# 03-ETHERNET.net
KiCad netlist of a schematic drawn in Altium Designer
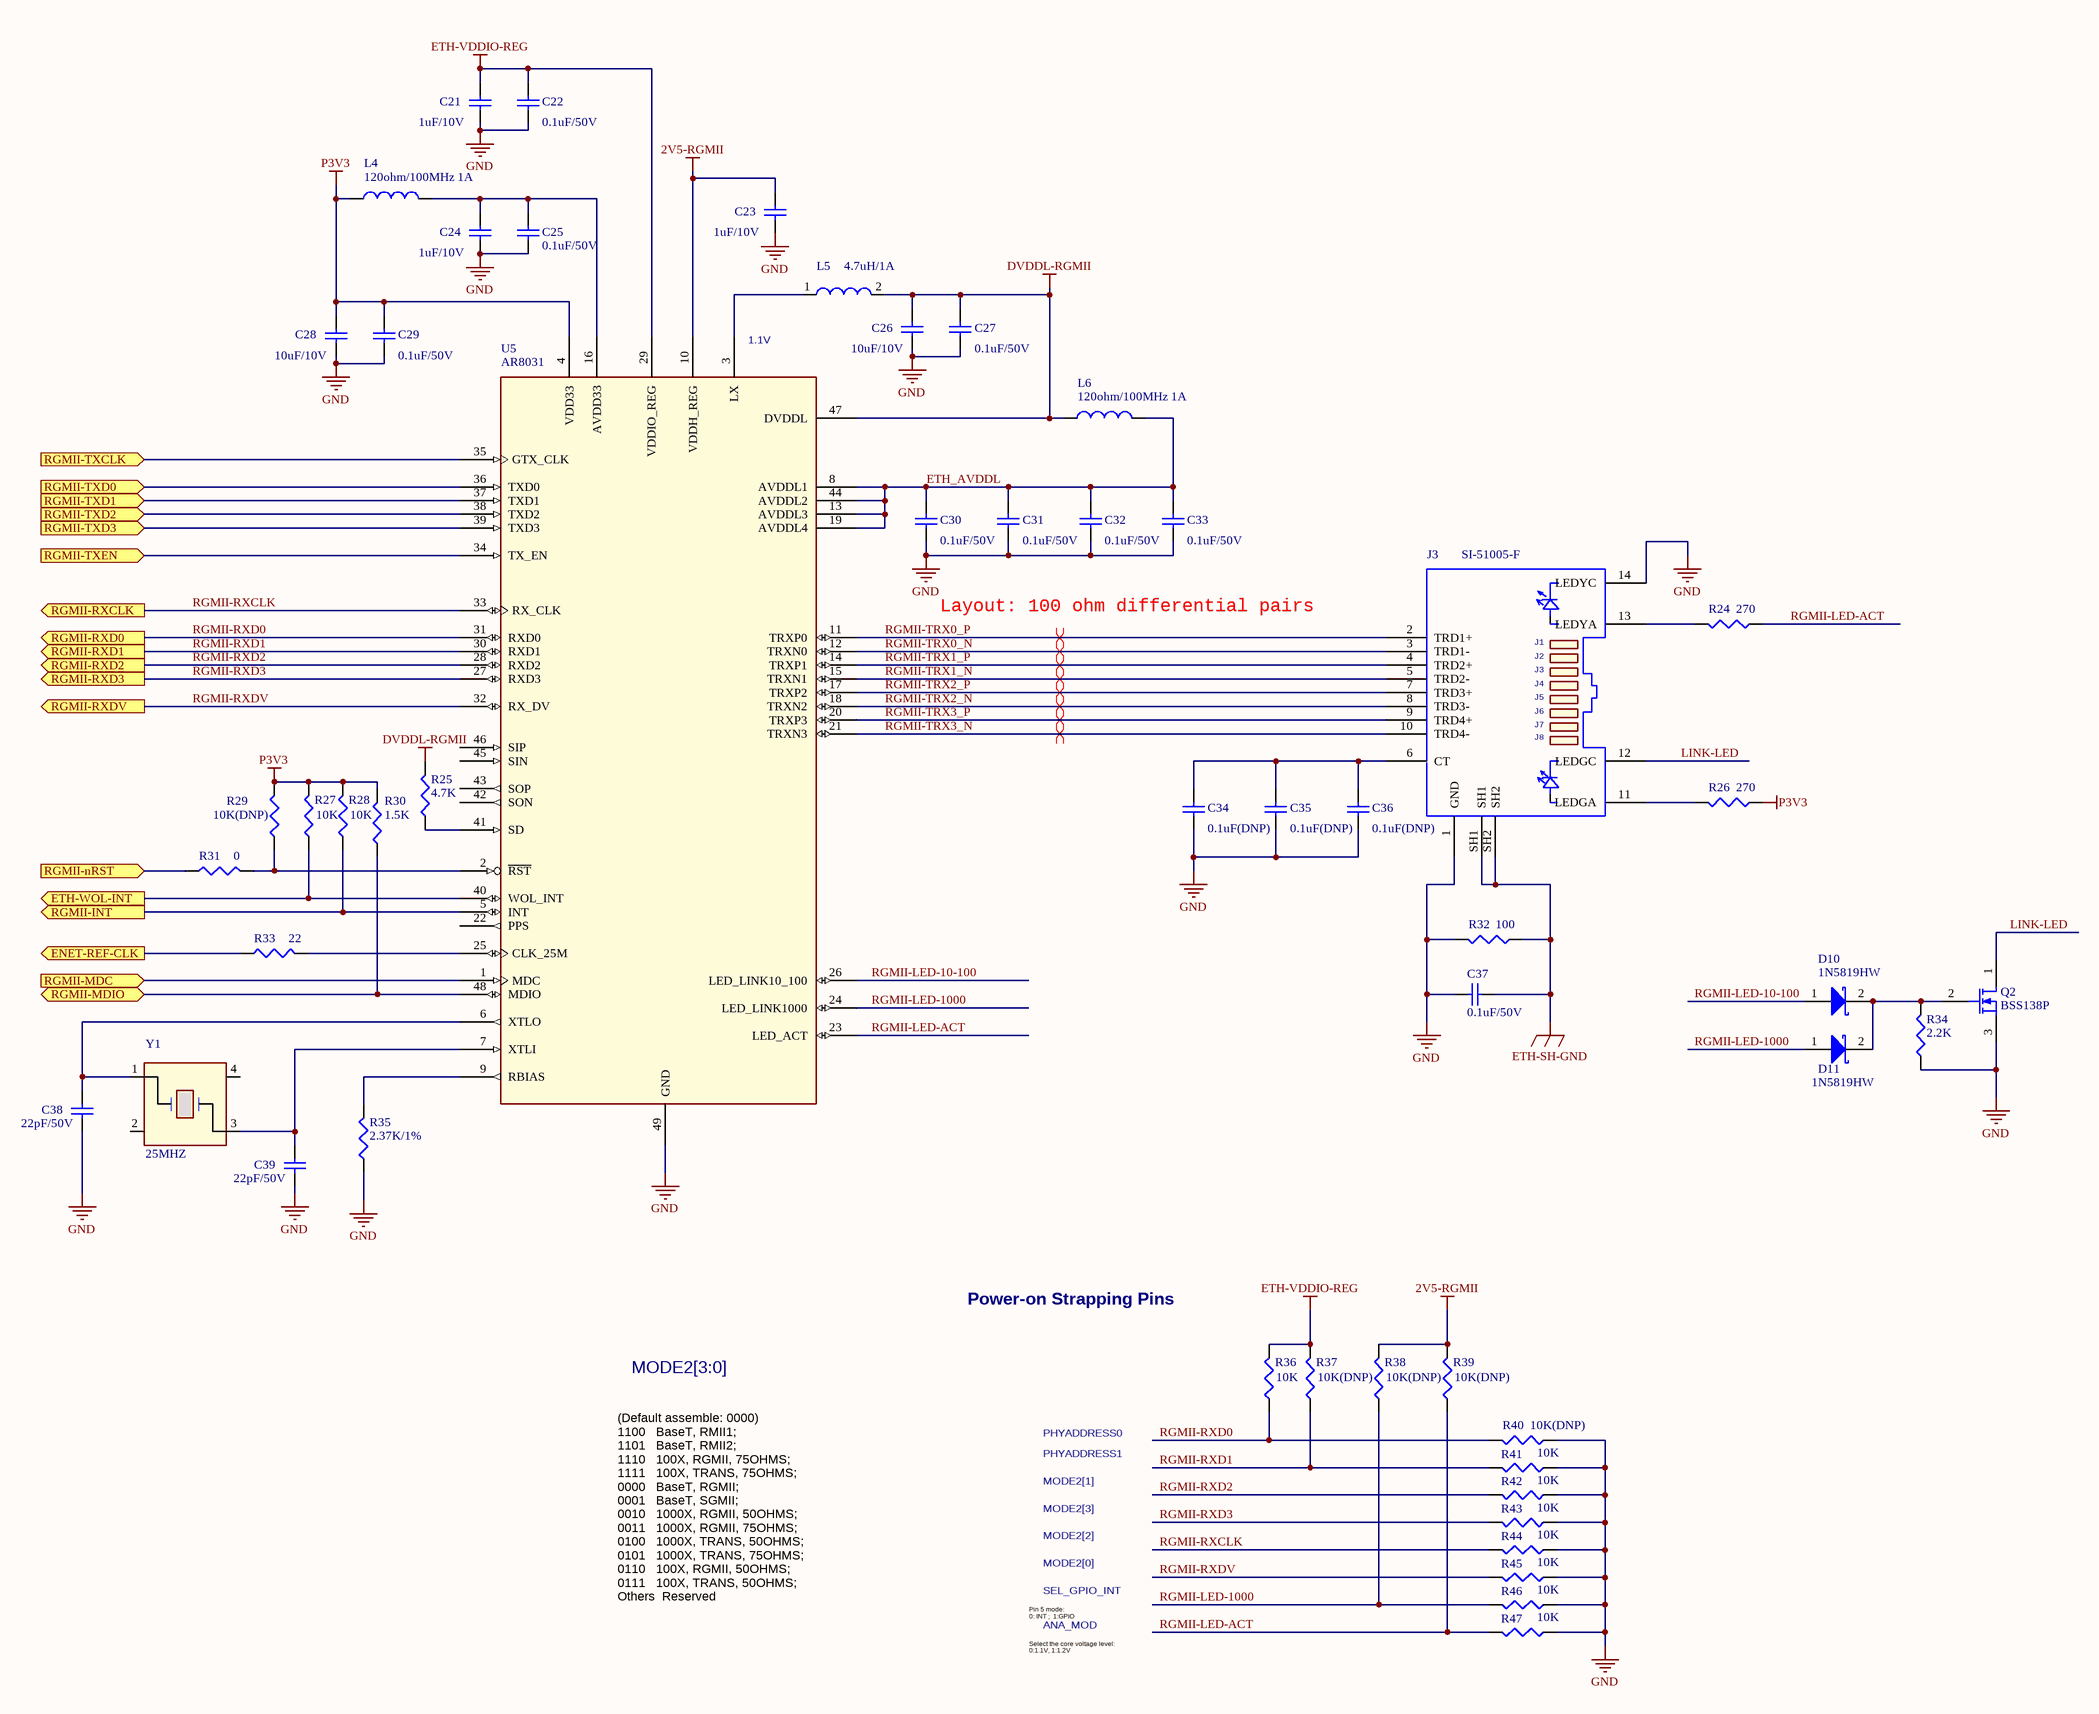
[diagram p0: 03-ETHERNET.SchDoc]

(export (version "E")
  (design (tool "Eeschema 10.0.6"))
  (components
    (comp (ref "C21")
      (value "1uF/10V")
      (footprint "0402")
      (description "Capacitor")
      (fields (field (name "PUBLISHER") "Altium Limited"))
      (libsource (lib "Miscellaneous Devices") (part "Cap"))
    )
    (comp (ref "C22")
      (value "0.1uF/50V")
      (footprint "0402")
      (description "Capacitor")
      (fields (field (name "PUBLISHER") "Altium Limited"))
      (libsource (lib "Miscellaneous Devices") (part "Cap"))
    )
    (comp (ref "C23")
      (value "1uF/10V")
      (footprint "0402")
      (description "Capacitor")
      (fields (field (name "PUBLISHER") "Altium Limited"))
      (libsource (lib "Miscellaneous Devices") (part "Cap"))
    )
    (comp (ref "C24")
      (value "1uF/10V")
      (footprint "0402")
      (description "Capacitor")
      (fields (field (name "PUBLISHER") "Altium Limited"))
      (libsource (lib "Miscellaneous Devices") (part "Cap"))
    )
    (comp (ref "C25")
      (value "0.1uF/50V")
      (footprint "0402")
      (description "Capacitor")
      (fields (field (name "PUBLISHER") "Altium Limited"))
      (libsource (lib "Miscellaneous Devices") (part "Cap"))
    )
    (comp (ref "C26")
      (value "10uF/10V")
      (footprint "0805")
      (description "Capacitor")
      (fields (field (name "PUBLISHER") "Altium Limited"))
      (libsource (lib "Miscellaneous Devices") (part "Cap"))
    )
    (comp (ref "C27")
      (value "0.1uF/50V")
      (footprint "0402")
      (description "Capacitor")
      (fields (field (name "PUBLISHER") "Altium Limited"))
      (libsource (lib "Miscellaneous Devices") (part "Cap"))
    )
    (comp (ref "C28")
      (value "10uF/10V")
      (footprint "0805")
      (description "Capacitor")
      (fields (field (name "PUBLISHER") "Altium Limited"))
      (libsource (lib "Miscellaneous Devices") (part "Cap"))
    )
    (comp (ref "C29")
      (value "0.1uF/50V")
      (footprint "0402")
      (description "Capacitor")
      (fields (field (name "PUBLISHER") "Altium Limited"))
      (libsource (lib "Miscellaneous Devices") (part "Cap"))
    )
    (comp (ref "C30")
      (value "0.1uF/50V")
      (footprint "0402")
      (description "Capacitor")
      (fields (field (name "PUBLISHER") "Altium Limited"))
      (libsource (lib "Miscellaneous Devices") (part "Cap"))
    )
    (comp (ref "C31")
      (value "0.1uF/50V")
      (footprint "0402")
      (description "Capacitor")
      (fields (field (name "PUBLISHER") "Altium Limited"))
      (libsource (lib "Miscellaneous Devices") (part "Cap"))
    )
    (comp (ref "C32")
      (value "0.1uF/50V")
      (footprint "0402")
      (description "Capacitor")
      (fields (field (name "PUBLISHER") "Altium Limited"))
      (libsource (lib "Miscellaneous Devices") (part "Cap"))
    )
    (comp (ref "C33")
      (value "0.1uF/50V")
      (footprint "0402")
      (description "Capacitor")
      (fields (field (name "PUBLISHER") "Altium Limited"))
      (libsource (lib "Miscellaneous Devices") (part "Cap"))
    )
    (comp (ref "C34")
      (value "0.1uF(DNP)")
      (footprint "0603")
      (description "Capacitor")
      (fields (field (name "PUBLISHER") "Altium Limited"))
      (libsource (lib "Miscellaneous Devices") (part "Cap"))
    )
    (comp (ref "C35")
      (value "0.1uF(DNP)")
      (footprint "0603")
      (description "Capacitor")
      (fields (field (name "PUBLISHER") "Altium Limited"))
      (libsource (lib "Miscellaneous Devices") (part "Cap"))
    )
    (comp (ref "C36")
      (value "0.1uF(DNP)")
      (footprint "0603")
      (description "Capacitor")
      (fields (field (name "PUBLISHER") "Altium Limited"))
      (libsource (lib "Miscellaneous Devices") (part "Cap"))
    )
    (comp (ref "C37")
      (value "0.1uF/50V")
      (footprint "0402")
      (description "Capacitor")
      (fields (field (name "PUBLISHER") "Altium Limited"))
      (libsource (lib "Miscellaneous Devices") (part "Cap"))
    )
    (comp (ref "C38")
      (value "22pF/50V")
      (footprint "0402")
      (description "Capacitor")
      (fields (field (name "PUBLISHER") "Altium Limited"))
      (libsource (lib "Miscellaneous Devices") (part "Cap"))
    )
    (comp (ref "C39")
      (value "22pF/50V")
      (footprint "0402")
      (description "Capacitor")
      (fields (field (name "PUBLISHER") "Altium Limited"))
      (libsource (lib "Miscellaneous Devices") (part "Cap"))
    )
    (comp (ref "D10")
      (value "1N5819HW")
      (footprint "1N5819")
      (description "Schottky Rectifier")
      (libsource (lib "Miscellaneous Devices") (part "Diode 11DQ03"))
    )
    (comp (ref "D11")
      (value "1N5819HW")
      (footprint "1N5819")
      (description "Schottky Rectifier")
      (libsource (lib "Miscellaneous Devices") (part "Diode 11DQ03"))
    )
    (comp (ref "J3")
      (value "SI-51005-F")
      (footprint "SI-51005-F")
      (libsource (lib "Schlib") (part "SI-51005-F"))
    )
    (comp (ref "L4")
      (value "120ohm/100MHz 1A")
      (footprint "0603")
      (description "Inductor")
      (fields (field (name "PUBLISHER") "Altium Limited"))
      (libsource (lib "Miscellaneous Devices") (part "Inductor"))
    )
    (comp (ref "L5")
      (value "4.7uH/1A")
      (footprint "IND-4.7UH-1A")
      (description "IND PWR 4.7UH@1MHZ 1A 20% SMD")
      (fields (field (name "TOLERANCE") "20%"))
      (libsource (lib "*") (part "INDUCTOR"))
    )
    (comp (ref "L6")
      (value "120ohm/100MHz 1A")
      (footprint "0603")
      (description "Inductor")
      (fields (field (name "PUBLISHER") "Altium Limited"))
      (libsource (lib "Miscellaneous Devices") (part "Inductor"))
    )
    (comp (ref "Q2")
      (value "BSS138P")
      (footprint "NPN")
      (description "N-Channel MOSFET")
      (fields (field (name "PUBLISHER") "Altium Limited"))
      (libsource (lib "Miscellaneous Devices") (part "MOSFET-N"))
    )
    (comp (ref "R24") (value "270") (footprint "0402") (libsource (lib "*") (part "CR16-1003FM")))
    (comp (ref "R25") (value "4.7K") (footprint "0402") (libsource (lib "*") (part "CR16-1003FM")))
    (comp (ref "R26") (value "270") (footprint "0402") (libsource (lib "*") (part "CR16-1003FM")))
    (comp (ref "R27") (value "10K") (footprint "0402") (libsource (lib "*") (part "CR16-1003FM")))
    (comp (ref "R28") (value "10K") (footprint "0402") (libsource (lib "*") (part "CR16-1003FM")))
    (comp (ref "R29") (value "10K(DNP)") (footprint "0402") (libsource (lib "*") (part "CR16-1003FM")))
    (comp (ref "R30") (value "1.5K") (footprint "0402") (libsource (lib "*") (part "CR16-1003FM")))
    (comp (ref "R31") (value "0") (footprint "0402") (libsource (lib "*") (part "CR16-1003FM")))
    (comp (ref "R32") (value "100") (footprint "0402") (libsource (lib "*") (part "CR16-1003FM")))
    (comp (ref "R33") (value "22") (footprint "0402") (libsource (lib "*") (part "CR16-1003FM")))
    (comp (ref "R34") (value "2.2K") (footprint "0402") (libsource (lib "*") (part "CR16-1003FM")))
    (comp (ref "R35") (value "2.37K/1%") (footprint "0402") (libsource (lib "*") (part "CR16-1003FM")))
    (comp (ref "R36") (value "10K") (footprint "0402") (libsource (lib "*") (part "CR16-1003FM")))
    (comp (ref "R37") (value "10K(DNP)") (footprint "0402") (libsource (lib "*") (part "CR16-1003FM")))
    (comp (ref "R38") (value "10K(DNP)") (footprint "0402") (libsource (lib "*") (part "CR16-1003FM")))
    (comp (ref "R39") (value "10K(DNP)") (footprint "0402") (libsource (lib "*") (part "CR16-1003FM")))
    (comp (ref "R40") (value "10K(DNP)") (footprint "0402") (libsource (lib "*") (part "CR16-1003FM")))
    (comp (ref "R41") (value "10K") (footprint "0402") (libsource (lib "*") (part "CR16-1003FM")))
    (comp (ref "R42") (value "10K") (footprint "0402") (libsource (lib "*") (part "CR16-1003FM")))
    (comp (ref "R43") (value "10K") (footprint "0402") (libsource (lib "*") (part "CR16-1003FM")))
    (comp (ref "R44") (value "10K") (footprint "0402") (libsource (lib "*") (part "CR16-1003FM")))
    (comp (ref "R45") (value "10K") (footprint "0402") (libsource (lib "*") (part "CR16-1003FM")))
    (comp (ref "R46") (value "10K") (footprint "0402") (libsource (lib "*") (part "CR16-1003FM")))
    (comp (ref "R47") (value "10K") (footprint "0402") (libsource (lib "*") (part "CR16-1003FM")))
    (comp (ref "U5")
      (value "AR8031")
      (footprint "QFN48")
      (description "IC XCVR ETHERNET PHY 10/100/1000G-BIT 3.3V QFN48")
      (libsource (lib "*") (part "AR8031_QFN48"))
    )
    (comp (ref "Y1")
      (value "25MHZ")
      (footprint "XTAL4_SX_3225")
      (description "XTAL 25MHZ -- -- SMT")
      (libsource (lib "*") (part "XTAL_13Y"))
    )
  )
  (nets
    (net (code "1") (name "/ENET-REF-CLK") (class "Default")
      (node (ref "R33") (pin "1") (pinfunction "1_1") (pintype "passive"))
    )
    (net (code "2") (name "/ETH-WOL-INT") (class "Default")
      (node (ref "R27") (pin "1") (pinfunction "1_1") (pintype "passive"))
      (node (ref "U5") (pin "40") (pinfunction "WOL_INT_40") (pintype "bidirectional"))
    )
    (net (code "3") (name "/ETH_AVDDL") (class "Default")
      (node (ref "C30") (pin "1") (pinfunction "1_1") (pintype "passive"))
      (node (ref "C31") (pin "1") (pinfunction "1_1") (pintype "passive"))
      (node (ref "C32") (pin "1") (pinfunction "1_1") (pintype "passive"))
      (node (ref "C33") (pin "1") (pinfunction "1_1") (pintype "passive"))
      (node (ref "L6") (pin "2") (pinfunction "2_2") (pintype "passive"))
      (node (ref "U5") (pin "13") (pinfunction "AVDDL3_13") (pintype "power_in"))
      (node (ref "U5") (pin "19") (pinfunction "AVDDL4_19") (pintype "power_in"))
      (node (ref "U5") (pin "44") (pinfunction "AVDDL2_44") (pintype "power_in"))
      (node (ref "U5") (pin "8") (pinfunction "AVDDL1_8") (pintype "power_in"))
    )
    (net (code "4") (name "/LINK-LED") (class "Default")
      (node (ref "J3") (pin "12") (pinfunction "LEDGC_12") (pintype "passive"))
      (node (ref "Q2") (pin "1") (pinfunction "D_1") (pintype "passive"))
    )
    (net (code "5") (name "/RGMII-INT") (class "Default")
      (node (ref "R28") (pin "1") (pinfunction "1_1") (pintype "passive"))
      (node (ref "U5") (pin "5") (pinfunction "INT_5") (pintype "bidirectional"))
    )
    (net (code "6") (name "/RGMII-LED-10-100") (class "Default")
      (node (ref "D10") (pin "1") (pinfunction "A_1") (pintype "passive"))
      (node (ref "U5") (pin "26") (pinfunction "LED_LINK10_100_26") (pintype "bidirectional"))
    )
    (net (code "7") (name "/RGMII-LED-1000") (class "Default")
      (node (ref "D11") (pin "1") (pinfunction "A_1") (pintype "passive"))
      (node (ref "R38") (pin "1") (pinfunction "1_1") (pintype "passive"))
      (node (ref "R46") (pin "2") (pinfunction "2_2") (pintype "passive"))
      (node (ref "U5") (pin "24") (pinfunction "LED_LINK1000_24") (pintype "bidirectional"))
    )
    (net (code "8") (name "/RGMII-LED-ACT") (class "Default")
      (node (ref "R24") (pin "1") (pinfunction "1_1") (pintype "passive"))
      (node (ref "R39") (pin "1") (pinfunction "1_1") (pintype "passive"))
      (node (ref "R47") (pin "2") (pinfunction "2_2") (pintype "passive"))
      (node (ref "U5") (pin "23") (pinfunction "LED_ACT_23") (pintype "bidirectional"))
    )
    (net (code "9") (name "/RGMII-MDC") (class "Default")
      (node (ref "U5") (pin "1") (pinfunction "MDC_1") (pintype "input"))
    )
    (net (code "10") (name "/RGMII-MDIO") (class "Default")
      (node (ref "R30") (pin "1") (pinfunction "1_1") (pintype "passive"))
      (node (ref "U5") (pin "48") (pinfunction "MDIO_48") (pintype "bidirectional"))
    )
    (net (code "11") (name "/RGMII-RXCLK") (class "Default")
      (node (ref "R44") (pin "2") (pinfunction "2_2") (pintype "passive"))
      (node (ref "U5") (pin "33") (pinfunction "RX_CLK_33") (pintype "bidirectional"))
    )
    (net (code "12") (name "/RGMII-RXD0") (class "Default")
      (node (ref "R36") (pin "1") (pinfunction "1_1") (pintype "passive"))
      (node (ref "R40") (pin "2") (pinfunction "2_2") (pintype "passive"))
      (node (ref "U5") (pin "31") (pinfunction "RXD0_31") (pintype "bidirectional"))
    )
    (net (code "13") (name "/RGMII-RXD1") (class "Default")
      (node (ref "R37") (pin "1") (pinfunction "1_1") (pintype "passive"))
      (node (ref "R41") (pin "2") (pinfunction "2_2") (pintype "passive"))
      (node (ref "U5") (pin "30") (pinfunction "RXD1_30") (pintype "bidirectional"))
    )
    (net (code "14") (name "/RGMII-RXD2") (class "Default")
      (node (ref "R42") (pin "2") (pinfunction "2_2") (pintype "passive"))
      (node (ref "U5") (pin "28") (pinfunction "RXD2_28") (pintype "bidirectional"))
    )
    (net (code "15") (name "/RGMII-RXD3") (class "Default")
      (node (ref "R43") (pin "2") (pinfunction "2_2") (pintype "passive"))
      (node (ref "U5") (pin "27") (pinfunction "RXD3_27") (pintype "bidirectional"))
    )
    (net (code "16") (name "/RGMII-RXDV") (class "Default")
      (node (ref "R45") (pin "2") (pinfunction "2_2") (pintype "passive"))
      (node (ref "U5") (pin "32") (pinfunction "RX_DV_32") (pintype "bidirectional"))
    )
    (net (code "17") (name "/RGMII-TRX0_N") (class "Default")
      (node (ref "J3") (pin "3") (pinfunction "TRD1-_3") (pintype "passive"))
      (node (ref "U5") (pin "12") (pinfunction "TRXN0_12") (pintype "bidirectional"))
    )
    (net (code "18") (name "/RGMII-TRX0_P") (class "Default")
      (node (ref "J3") (pin "2") (pinfunction "TRD1+_2") (pintype "passive"))
      (node (ref "U5") (pin "11") (pinfunction "TRXP0_11") (pintype "bidirectional"))
    )
    (net (code "19") (name "/RGMII-TRX1_N") (class "Default")
      (node (ref "J3") (pin "5") (pinfunction "TRD2-_5") (pintype "passive"))
      (node (ref "U5") (pin "15") (pinfunction "TRXN1_15") (pintype "bidirectional"))
    )
    (net (code "20") (name "/RGMII-TRX1_P") (class "Default")
      (node (ref "J3") (pin "4") (pinfunction "TRD2+_4") (pintype "passive"))
      (node (ref "U5") (pin "14") (pinfunction "TRXP1_14") (pintype "bidirectional"))
    )
    (net (code "21") (name "/RGMII-TRX2_N") (class "Default")
      (node (ref "J3") (pin "8") (pinfunction "TRD3-_8") (pintype "passive"))
      (node (ref "U5") (pin "18") (pinfunction "TRXN2_18") (pintype "bidirectional"))
    )
    (net (code "22") (name "/RGMII-TRX2_P") (class "Default")
      (node (ref "J3") (pin "7") (pinfunction "TRD3+_7") (pintype "passive"))
      (node (ref "U5") (pin "17") (pinfunction "TRXP2_17") (pintype "bidirectional"))
    )
    (net (code "23") (name "/RGMII-TRX3_N") (class "Default")
      (node (ref "J3") (pin "10") (pinfunction "TRD4-_10") (pintype "passive"))
      (node (ref "U5") (pin "21") (pinfunction "TRXN3_21") (pintype "bidirectional"))
    )
    (net (code "24") (name "/RGMII-TRX3_P") (class "Default")
      (node (ref "J3") (pin "9") (pinfunction "TRD4+_9") (pintype "passive"))
      (node (ref "U5") (pin "20") (pinfunction "TRXP3_20") (pintype "bidirectional"))
    )
    (net (code "25") (name "/RGMII-TXCLK") (class "Default")
      (node (ref "U5") (pin "35") (pinfunction "GTX_CLK_35") (pintype "input"))
    )
    (net (code "26") (name "/RGMII-TXD0") (class "Default")
      (node (ref "U5") (pin "36") (pinfunction "TXD0_36") (pintype "input"))
    )
    (net (code "27") (name "/RGMII-TXD1") (class "Default")
      (node (ref "U5") (pin "37") (pinfunction "TXD1_37") (pintype "input"))
    )
    (net (code "28") (name "/RGMII-TXD2") (class "Default")
      (node (ref "U5") (pin "38") (pinfunction "TXD2_38") (pintype "input"))
    )
    (net (code "29") (name "/RGMII-TXD3") (class "Default")
      (node (ref "U5") (pin "39") (pinfunction "TXD3_39") (pintype "input"))
    )
    (net (code "30") (name "/RGMII-TXEN") (class "Default")
      (node (ref "U5") (pin "34") (pinfunction "TX_EN_34") (pintype "input"))
    )
    (net (code "31") (name "/RGMII-nRST") (class "Default")
      (node (ref "R31") (pin "1") (pinfunction "1_1") (pintype "passive"))
    )
    (net (code "32") (name "2V5-RGMII") (class "Default")
      (node (ref "C23") (pin "1") (pinfunction "1_1") (pintype "passive"))
      (node (ref "R38") (pin "2") (pinfunction "2_2") (pintype "passive"))
      (node (ref "R39") (pin "2") (pinfunction "2_2") (pintype "passive"))
      (node (ref "U5") (pin "10") (pinfunction "VDDH_REG_10") (pintype "power_in"))
    )
    (net (code "33") (name "DVDDL-RGMII") (class "Default")
      (node (ref "C26") (pin "1") (pinfunction "1_1") (pintype "passive"))
      (node (ref "C27") (pin "1") (pinfunction "1_1") (pintype "passive"))
      (node (ref "L5") (pin "2") (pinfunction "2_2") (pintype "passive"))
      (node (ref "L6") (pin "1") (pinfunction "1_1") (pintype "passive"))
      (node (ref "R25") (pin "2") (pinfunction "2_2") (pintype "passive"))
      (node (ref "U5") (pin "47") (pinfunction "DVDDL_47") (pintype "power_in"))
    )
    (net (code "34") (name "ETH-SH-GND") (class "Default")
      (node (ref "C37") (pin "2") (pinfunction "2_2") (pintype "passive"))
      (node (ref "J3") (pin "SH1") (pinfunction "SH1_SH1") (pintype "passive"))
      (node (ref "J3") (pin "SH2") (pinfunction "SH2_SH2") (pintype "passive"))
      (node (ref "R32") (pin "1") (pinfunction "1_1") (pintype "passive"))
    )
    (net (code "35") (name "ETH-VDDIO-REG") (class "Default")
      (node (ref "C21") (pin "1") (pinfunction "1_1") (pintype "passive"))
      (node (ref "C22") (pin "1") (pinfunction "1_1") (pintype "passive"))
      (node (ref "R36") (pin "2") (pinfunction "2_2") (pintype "passive"))
      (node (ref "R37") (pin "2") (pinfunction "2_2") (pintype "passive"))
      (node (ref "U5") (pin "29") (pinfunction "VDDIO_REG_29") (pintype "power_in"))
    )
    (net (code "36") (name "GND") (class "Default")
      (node (ref "C21") (pin "2") (pinfunction "2_2") (pintype "passive"))
      (node (ref "C22") (pin "2") (pinfunction "2_2") (pintype "passive"))
      (node (ref "C23") (pin "2") (pinfunction "2_2") (pintype "passive"))
      (node (ref "C24") (pin "2") (pinfunction "2_2") (pintype "passive"))
      (node (ref "C25") (pin "2") (pinfunction "2_2") (pintype "passive"))
      (node (ref "C26") (pin "2") (pinfunction "2_2") (pintype "passive"))
      (node (ref "C27") (pin "2") (pinfunction "2_2") (pintype "passive"))
      (node (ref "C28") (pin "2") (pinfunction "2_2") (pintype "passive"))
      (node (ref "C29") (pin "2") (pinfunction "2_2") (pintype "passive"))
      (node (ref "C30") (pin "2") (pinfunction "2_2") (pintype "passive"))
      (node (ref "C31") (pin "2") (pinfunction "2_2") (pintype "passive"))
      (node (ref "C32") (pin "2") (pinfunction "2_2") (pintype "passive"))
      (node (ref "C33") (pin "2") (pinfunction "2_2") (pintype "passive"))
      (node (ref "C34") (pin "2") (pinfunction "2_2") (pintype "passive"))
      (node (ref "C35") (pin "2") (pinfunction "2_2") (pintype "passive"))
      (node (ref "C36") (pin "2") (pinfunction "2_2") (pintype "passive"))
      (node (ref "C37") (pin "1") (pinfunction "1_1") (pintype "passive"))
      (node (ref "C38") (pin "2") (pinfunction "2_2") (pintype "passive"))
      (node (ref "C39") (pin "2") (pinfunction "2_2") (pintype "passive"))
      (node (ref "J3") (pin "1") (pinfunction "GND_1") (pintype "power_in"))
      (node (ref "J3") (pin "14") (pinfunction "LEDYC_14") (pintype "passive"))
      (node (ref "Q2") (pin "3") (pinfunction "S_3") (pintype "passive"))
      (node (ref "R32") (pin "2") (pinfunction "2_2") (pintype "passive"))
      (node (ref "R34") (pin "1") (pinfunction "1_1") (pintype "passive"))
      (node (ref "R35") (pin "1") (pinfunction "1_1") (pintype "passive"))
      (node (ref "R40") (pin "1") (pinfunction "1_1") (pintype "passive"))
      (node (ref "R41") (pin "1") (pinfunction "1_1") (pintype "passive"))
      (node (ref "R42") (pin "1") (pinfunction "1_1") (pintype "passive"))
      (node (ref "R43") (pin "1") (pinfunction "1_1") (pintype "passive"))
      (node (ref "R44") (pin "1") (pinfunction "1_1") (pintype "passive"))
      (node (ref "R45") (pin "1") (pinfunction "1_1") (pintype "passive"))
      (node (ref "R46") (pin "1") (pinfunction "1_1") (pintype "passive"))
      (node (ref "R47") (pin "1") (pinfunction "1_1") (pintype "passive"))
      (node (ref "U5") (pin "49") (pinfunction "GND_49") (pintype "power_in"))
    )
    (net (code "37") (name "Net-(D10-K)") (class "Default")
      (node (ref "D10") (pin "2") (pinfunction "K_2") (pintype "passive"))
      (node (ref "D11") (pin "2") (pinfunction "K_2") (pintype "passive"))
      (node (ref "Q2") (pin "2") (pinfunction "G_2") (pintype "passive"))
      (node (ref "R34") (pin "2") (pinfunction "2_2") (pintype "passive"))
    )
    (net (code "38") (name "Net-(J3-CT)") (class "Default")
      (node (ref "C34") (pin "1") (pinfunction "1_1") (pintype "passive"))
      (node (ref "C35") (pin "1") (pinfunction "1_1") (pintype "passive"))
      (node (ref "C36") (pin "1") (pinfunction "1_1") (pintype "passive"))
      (node (ref "J3") (pin "6") (pinfunction "CT_6") (pintype "passive"))
    )
    (net (code "39") (name "Net-(J3-LEDGA)") (class "Default")
      (node (ref "J3") (pin "11") (pinfunction "LEDGA_11") (pintype "passive"))
      (node (ref "R26") (pin "2") (pinfunction "2_2") (pintype "passive"))
    )
    (net (code "40") (name "Net-(J3-LEDYA)") (class "Default")
      (node (ref "J3") (pin "13") (pinfunction "LEDYA_13") (pintype "passive"))
      (node (ref "R24") (pin "2") (pinfunction "2_2") (pintype "passive"))
    )
    (net (code "41") (name "Net-(U5-AVDD33)") (class "Default")
      (node (ref "C24") (pin "1") (pinfunction "1_1") (pintype "passive"))
      (node (ref "C25") (pin "1") (pinfunction "1_1") (pintype "passive"))
      (node (ref "L4") (pin "2") (pinfunction "2_2") (pintype "passive"))
      (node (ref "U5") (pin "16") (pinfunction "AVDD33_16") (pintype "power_in"))
    )
    (net (code "42") (name "Net-(U5-CLK_25M)") (class "Default")
      (node (ref "R33") (pin "2") (pinfunction "2_2") (pintype "passive"))
      (node (ref "U5") (pin "25") (pinfunction "CLK_25M_25") (pintype "bidirectional"))
    )
    (net (code "43") (name "Net-(U5-LX)") (class "Default")
      (node (ref "L5") (pin "1") (pinfunction "1_1") (pintype "passive"))
      (node (ref "U5") (pin "3") (pinfunction "LX_3") (pintype "power_in"))
    )
    (net (code "44") (name "Net-(U5-RBIAS)") (class "Default")
      (node (ref "R35") (pin "2") (pinfunction "2_2") (pintype "passive"))
      (node (ref "U5") (pin "9") (pinfunction "RBIAS_9") (pintype "output"))
    )
    (net (code "45") (name "Net-(U5-SD)") (class "Default")
      (node (ref "R25") (pin "1") (pinfunction "1_1") (pintype "passive"))
      (node (ref "U5") (pin "41") (pinfunction "SD_41") (pintype "input"))
    )
    (net (code "46") (name "Net-(U5-XTLI)") (class "Default")
      (node (ref "C39") (pin "1") (pinfunction "1_1") (pintype "passive"))
      (node (ref "U5") (pin "7") (pinfunction "XTLI_7") (pintype "input"))
      (node (ref "Y1") (pin "3") (pinfunction "3_3") (pintype "passive"))
    )
    (net (code "47") (name "Net-(U5-XTLO)") (class "Default")
      (node (ref "C38") (pin "1") (pinfunction "1_1") (pintype "passive"))
      (node (ref "U5") (pin "6") (pinfunction "XTLO_6") (pintype "output"))
      (node (ref "Y1") (pin "1") (pinfunction "1_1") (pintype "passive"))
    )
    (net (code "48") (name "Net-(U5-~{RST})") (class "Default")
      (node (ref "R29") (pin "1") (pinfunction "1_1") (pintype "passive"))
      (node (ref "R31") (pin "2") (pinfunction "2_2") (pintype "passive"))
      (node (ref "U5") (pin "2") (pinfunction "~{RST}_2") (pintype "input"))
    )
    (net (code "49") (name "P3V3") (class "Default")
      (node (ref "C28") (pin "1") (pinfunction "1_1") (pintype "passive"))
      (node (ref "C29") (pin "1") (pinfunction "1_1") (pintype "passive"))
      (node (ref "L4") (pin "1") (pinfunction "1_1") (pintype "passive"))
      (node (ref "R26") (pin "1") (pinfunction "1_1") (pintype "passive"))
      (node (ref "R27") (pin "2") (pinfunction "2_2") (pintype "passive"))
      (node (ref "R28") (pin "2") (pinfunction "2_2") (pintype "passive"))
      (node (ref "R29") (pin "2") (pinfunction "2_2") (pintype "passive"))
      (node (ref "R30") (pin "2") (pinfunction "2_2") (pintype "passive"))
      (node (ref "U5") (pin "4") (pinfunction "VDD33_4") (pintype "power_in"))
    )
    (net (code "50") (name "unconnected-(U5-PPS-Pad22)") (class "Default")
      (node (ref "U5") (pin "22") (pinfunction "PPS_22") (pintype "output"))
    )
    (net (code "51") (name "unconnected-(U5-SIN-Pad45)") (class "Default")
      (node (ref "U5") (pin "45") (pinfunction "SIN_45") (pintype "input"))
    )
    (net (code "52") (name "unconnected-(U5-SIP-Pad46)") (class "Default")
      (node (ref "U5") (pin "46") (pinfunction "SIP_46") (pintype "input"))
    )
    (net (code "53") (name "unconnected-(U5-SON-Pad42)") (class "Default")
      (node (ref "U5") (pin "42") (pinfunction "SON_42") (pintype "output"))
    )
    (net (code "54") (name "unconnected-(U5-SOP-Pad43)") (class "Default")
      (node (ref "U5") (pin "43") (pinfunction "SOP_43") (pintype "output"))
    )
    (net (code "55") (name "unconnected-(Y1-Pad2)") (class "Default")
      (node (ref "Y1") (pin "2") (pinfunction "2_2") (pintype "passive"))
    )
    (net (code "56") (name "unconnected-(Y1-Pad4)") (class "Default")
      (node (ref "Y1") (pin "4") (pinfunction "4_4") (pintype "passive"))
    )
  )
)
